# Encoder.net
KiCad netlist of a schematic drawn in EAGLE
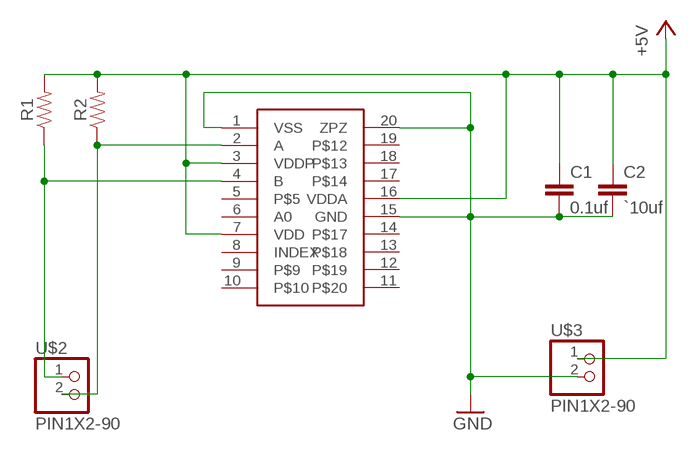
[diagram p0: schematic, sheet 1]

(export (version "E")
  (design (tool "Eeschema 10.0.6"))
  (components
    (comp (ref "C1")
      (value "0.1uf")
      (footprint "eagle-import:0805")
      (libsource (lib "eagle-import") (part "CAP-0805"))
    )
    (comp (ref "C2")
      (value "`10uf")
      (footprint "eagle-import:0805")
      (libsource (lib "eagle-import") (part "CAP-0805"))
    )
    (comp (ref "R1")
      (value "RESISTOR0805")
      (footprint "eagle-import:0805")
      (libsource (lib "eagle-import") (part "RESISTOR0805"))
    )
    (comp (ref "R2")
      (value "RESISTOR0805")
      (footprint "eagle-import:0805")
      (libsource (lib "eagle-import") (part "RESISTOR0805"))
    )
    (comp (ref "U$1")
      (value "AS5304")
      (footprint "eagle-import:SSOP20")
      (libsource (lib "eagle-import") (part "AS5304"))
    )
    (comp (ref "U$2")
      (value "PIN1X2-90")
      (footprint "eagle-import:1X02_90")
      (libsource (lib "eagle-import") (part "PIN1X2-90"))
    )
    (comp (ref "U$3")
      (value "PIN1X2-90")
      (footprint "eagle-import:1X02_90")
      (libsource (lib "eagle-import") (part "PIN1X2-90"))
    )
  )
  (nets
    (net (code "1") (name "+5V") (class "Default")
      (node (ref "C1") (pin "1") (pinfunction "1_1") (pintype "passive"))
      (node (ref "C2") (pin "1") (pinfunction "1_1") (pintype "passive"))
      (node (ref "R1") (pin "2") (pinfunction "2_2") (pintype "passive"))
      (node (ref "R2") (pin "2") (pinfunction "2_2") (pintype "passive"))
      (node (ref "U$1") (pin "16") (pinfunction "VDDA_16") (pintype "bidirectional"))
      (node (ref "U$1") (pin "3") (pinfunction "VDDP_3") (pintype "bidirectional"))
      (node (ref "U$1") (pin "7") (pinfunction "VDD_7") (pintype "bidirectional"))
      (node (ref "U$3") (pin "1") (pinfunction "1_1") (pintype "passive"))
    )
    (net (code "2") (name "GND") (class "Default")
      (node (ref "C1") (pin "2") (pinfunction "2_2") (pintype "passive"))
      (node (ref "C2") (pin "2") (pinfunction "2_2") (pintype "passive"))
      (node (ref "U$1") (pin "1") (pinfunction "VSS_1") (pintype "bidirectional"))
      (node (ref "U$1") (pin "15") (pinfunction "GND_15") (pintype "bidirectional"))
      (node (ref "U$1") (pin "20") (pinfunction "ZPZ_20") (pintype "bidirectional"))
      (node (ref "U$3") (pin "2") (pinfunction "2_2") (pintype "passive"))
    )
    (net (code "3") (name "Net-(U$1-A)") (class "Default")
      (node (ref "R2") (pin "1") (pinfunction "1_1") (pintype "passive"))
      (node (ref "U$1") (pin "2") (pinfunction "A_2") (pintype "bidirectional"))
      (node (ref "U$2") (pin "2") (pinfunction "2_2") (pintype "passive"))
    )
    (net (code "4") (name "Net-(U$1-B)") (class "Default")
      (node (ref "R1") (pin "1") (pinfunction "1_1") (pintype "passive"))
      (node (ref "U$1") (pin "4") (pinfunction "B_4") (pintype "bidirectional"))
      (node (ref "U$2") (pin "1") (pinfunction "1_1") (pintype "passive"))
    )
    (net (code "5") (name "unconnected-(U$1-A0-Pad6)") (class "Default")
      (node (ref "U$1") (pin "6") (pinfunction "A0_6") (pintype "bidirectional"))
    )
    (net (code "6") (name "unconnected-(U$1-INDEX-Pad8)") (class "Default")
      (node (ref "U$1") (pin "8") (pinfunction "INDEX_8") (pintype "bidirectional"))
    )
    (net (code "7") (name "unconnected-(U$1-P$5-Pad5)") (class "Default")
      (node (ref "U$1") (pin "5") (pinfunction "P$5_5") (pintype "bidirectional"))
    )
    (net (code "8") (name "unconnected-(U$1-P$9-Pad9)") (class "Default")
      (node (ref "U$1") (pin "9") (pinfunction "P$9_9") (pintype "bidirectional"))
    )
    (net (code "9") (name "unconnected-(U$1-P$10-Pad10)") (class "Default")
      (node (ref "U$1") (pin "10") (pinfunction "P$10_10") (pintype "bidirectional"))
    )
    (net (code "10") (name "unconnected-(U$1-P$12-Pad19)") (class "Default")
      (node (ref "U$1") (pin "19") (pinfunction "P$12_19") (pintype "bidirectional"))
    )
    (net (code "11") (name "unconnected-(U$1-P$13-Pad18)") (class "Default")
      (node (ref "U$1") (pin "18") (pinfunction "P$13_18") (pintype "bidirectional"))
    )
    (net (code "12") (name "unconnected-(U$1-P$14-Pad17)") (class "Default")
      (node (ref "U$1") (pin "17") (pinfunction "P$14_17") (pintype "bidirectional"))
    )
    (net (code "13") (name "unconnected-(U$1-P$17-Pad14)") (class "Default")
      (node (ref "U$1") (pin "14") (pinfunction "P$17_14") (pintype "bidirectional"))
    )
    (net (code "14") (name "unconnected-(U$1-P$18-Pad13)") (class "Default")
      (node (ref "U$1") (pin "13") (pinfunction "P$18_13") (pintype "bidirectional"))
    )
    (net (code "15") (name "unconnected-(U$1-P$19-Pad12)") (class "Default")
      (node (ref "U$1") (pin "12") (pinfunction "P$19_12") (pintype "bidirectional"))
    )
    (net (code "16") (name "unconnected-(U$1-P$20-Pad11)") (class "Default")
      (node (ref "U$1") (pin "11") (pinfunction "P$20_11") (pintype "bidirectional"))
    )
  )
)
